# 03_Battery_Management.net
KiCad netlist of a schematic drawn in Altium Designer
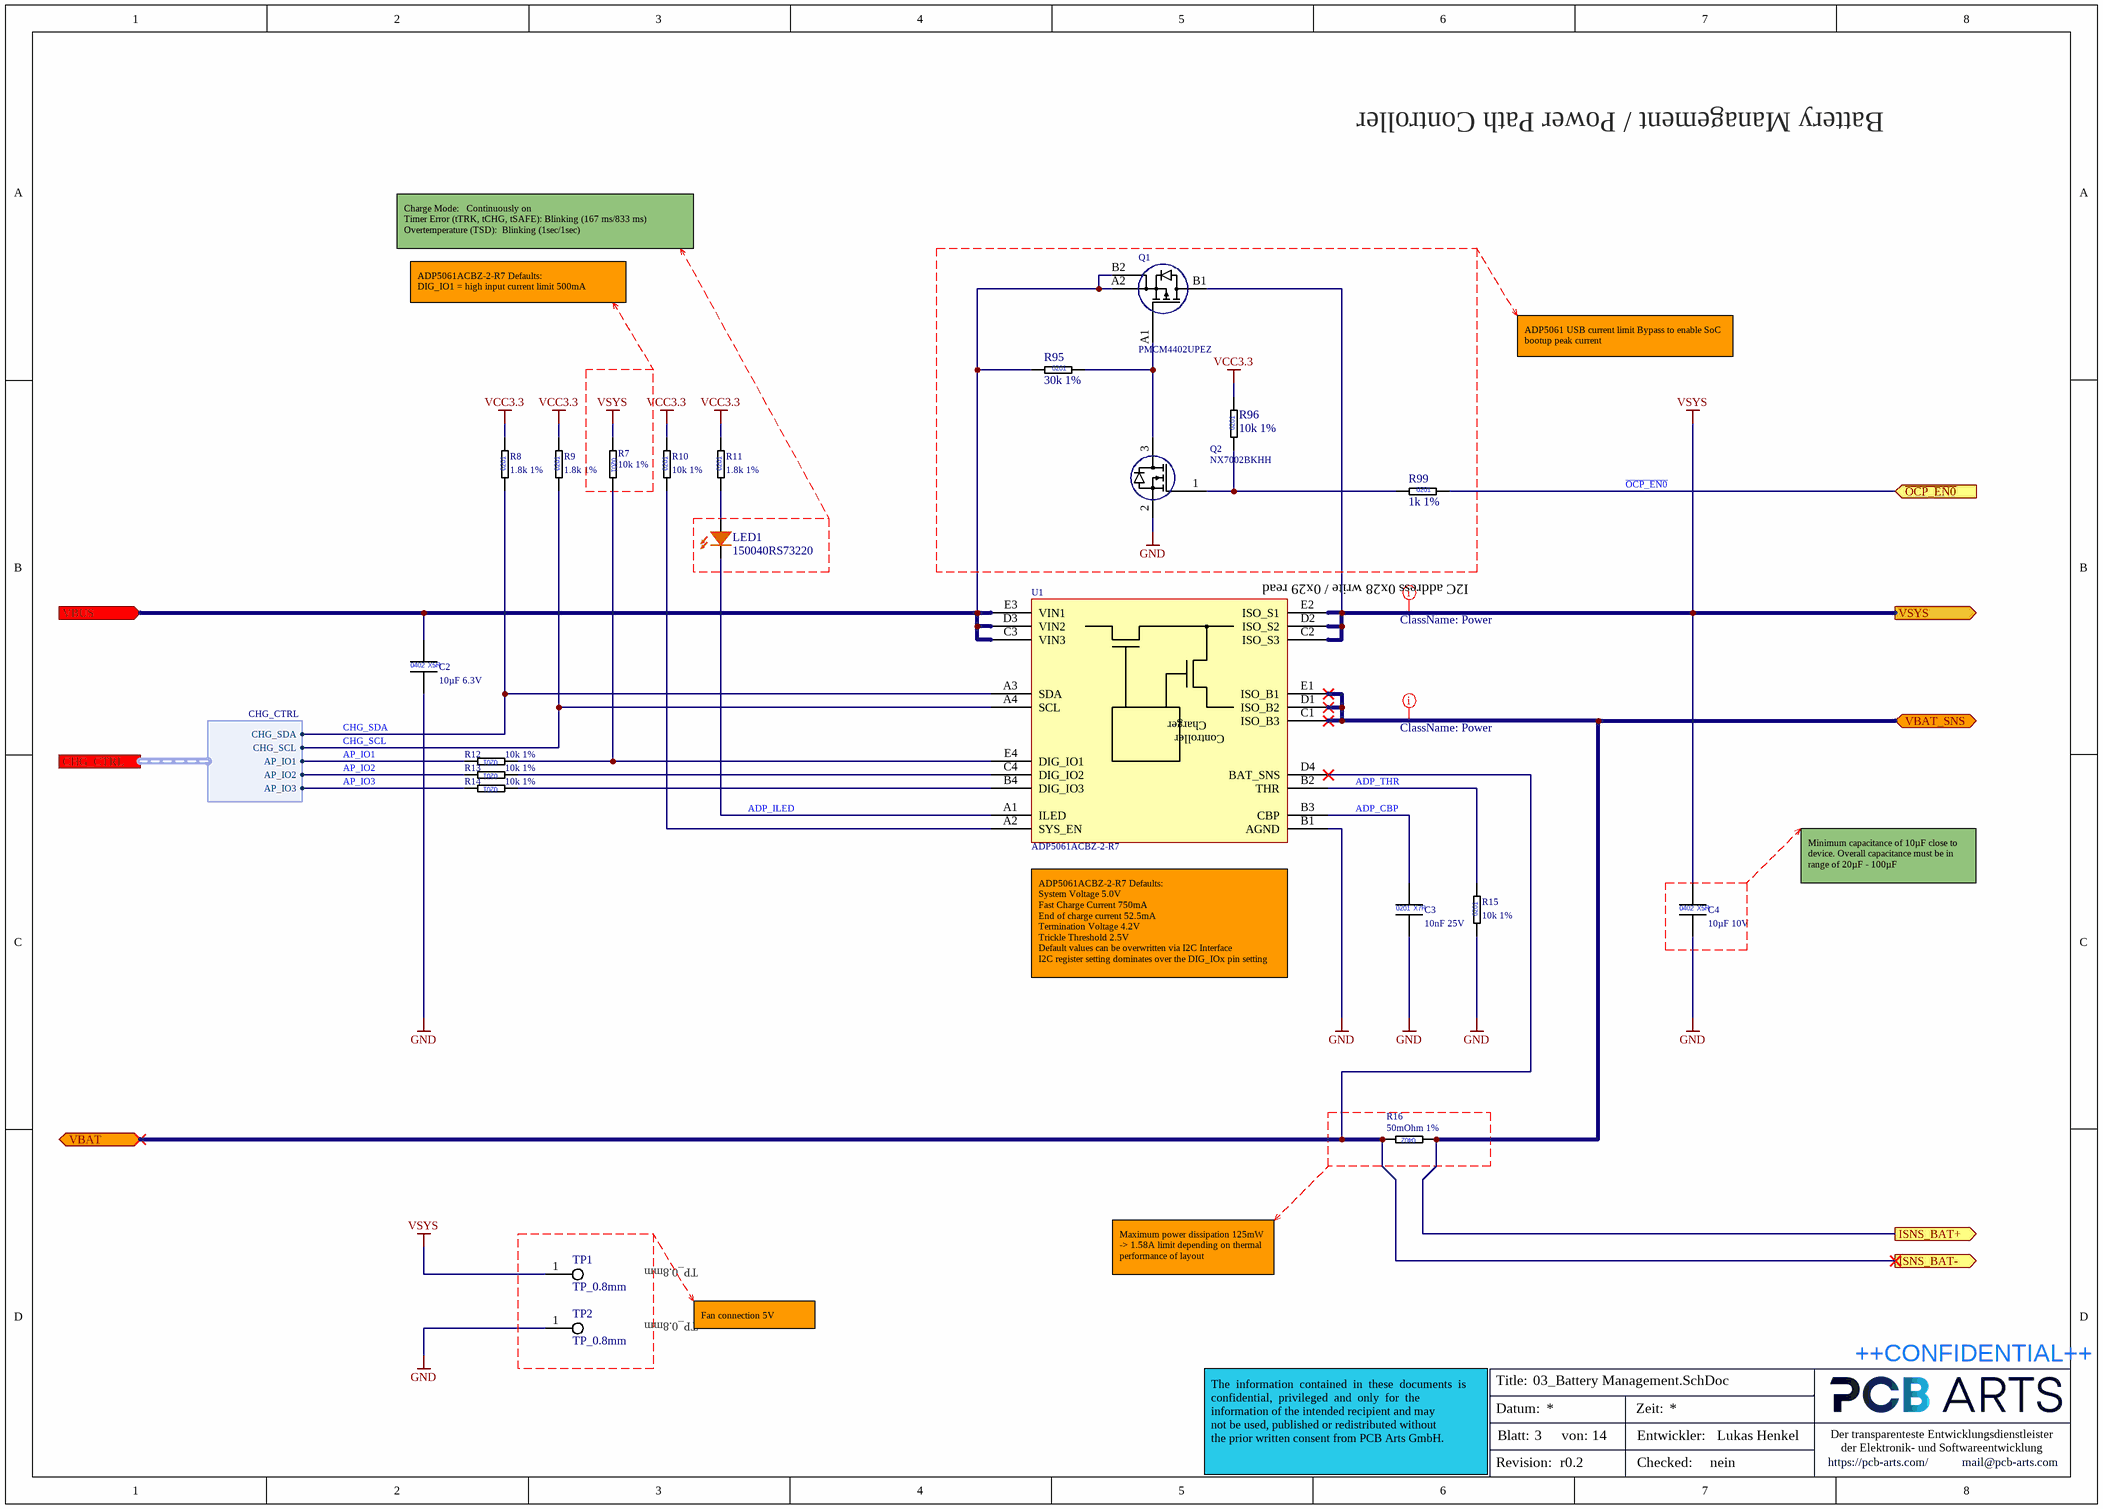
[diagram p0: 03_Battery Management.SchDoc]

(export (version "E")
  (design (tool "Eeschema 10.0.6"))
  (components
    (comp (ref "C2")
      (value "10µF 6.3V")
      (footprint "Zynq-Feather-HD:CAPC1005X06L")
      (description "Multilayer Ceramic Capacitors MLCC - SMD/SMT 0402 6.3VDC")
      (libsource (lib "Zynq-Feather-HD") (part "CAP_0402_10µ_6.3V"))
    )
    (comp (ref "C3")
      (value "10nF 25V")
      (footprint "Zynq-Feather-HD:CAPC0603X03L")
      (description "Multilayer Ceramic Capacitors MLCC - SMD/SMT 0201 25VDC")
      (libsource (lib "Zynq-Feather-HD") (part "CAP_0201_10nF_25V"))
    )
    (comp (ref "C4")
      (value "10µF 10V")
      (footprint "Zynq-Feather-HD:CAPC1005X06L")
      (description "Multilayer Ceramic Capacitors MLCC - SMD/SMT 0402 10VDC")
      (libsource (lib "Zynq-Feather-HD") (part "CAP_0402_10µ_10V"))
    )
    (comp (ref "LED1")
      (value "150040RS73220")
      (footprint "Zynq-Feather-HD:WL-SMCC_0402_H=0.25mm")
      (description "Standard LEDs - SMD WL-SMCC SMT LED Mono-color")
      (libsource (lib "Zynq-Feather-HD") (part "150040RS73220_SMD WL-SMCC SMT LED Mono-color"))
    )
    (comp (ref "Q1")
      (value "PMCM4402UPEZ")
      (footprint "zynq-feather-hd:BGA4C40P2X2_78X78X38")
      (description "20 V, P-channel Trench MOSFET")
      (libsource (lib "Zynq-Feather-HD") (part "PMCM4402UPEZ_PMOS 20V P-channel Trench MOSFET"))
    )
    (comp (ref "Q2")
      (value "NX7002BKHH")
      (footprint "Zynq-Feather-HD:DFN0606-3")
      (description "60 V, N-channel Trench MOSFET 2.8Ohm")
      (libsource (lib "Zynq-Feather-HD") (part "NX7002BKHH_NMOS 60V N-channel Trench MOSFET"))
    )
    (comp (ref "R7")
      (value "10k 1%")
      (footprint "Zynq-Feather-HD:RESC0603X03L")
      (description "Thick Film Resistors - SMD 10K OHM 1%")
      (libsource (lib "Zynq-Feather-HD") (part "RES_0201_10k_1%"))
    )
    (comp (ref "R8")
      (value "1.8k 1%")
      (footprint "Zynq-Feather-HD:RESC0603X03L")
      (description "Thick Film Resistors - SMD 1.8K OHM 1%")
      (libsource (lib "Zynq-Feather-HD") (part "RES_0201_1.8k_1%"))
    )
    (comp (ref "R9")
      (value "1.8k 1%")
      (footprint "Zynq-Feather-HD:RESC0603X03L")
      (description "Thick Film Resistors - SMD 1.8K OHM 1%")
      (libsource (lib "Zynq-Feather-HD") (part "RES_0201_1.8k_1%"))
    )
    (comp (ref "R10")
      (value "10k 1%")
      (footprint "Zynq-Feather-HD:RESC0603X03L")
      (description "Thick Film Resistors - SMD 10K OHM 1%")
      (libsource (lib "Zynq-Feather-HD") (part "RES_0201_10k_1%"))
    )
    (comp (ref "R11")
      (value "1.8k 1%")
      (footprint "Zynq-Feather-HD:RESC0603X03L")
      (description "Thick Film Resistors - SMD 1.8K OHM 1%")
      (libsource (lib "Zynq-Feather-HD") (part "RES_0201_1.8k_1%"))
    )
    (comp (ref "R12")
      (value "10k 1%")
      (footprint "Zynq-Feather-HD:RESC0603X03L")
      (description "Thick Film Resistors - SMD 10K OHM 1%")
      (libsource (lib "Zynq-Feather-HD") (part "RES_0201_10k_1%"))
    )
    (comp (ref "R13")
      (value "10k 1%")
      (footprint "Zynq-Feather-HD:RESC0603X03L")
      (description "Thick Film Resistors - SMD 10K OHM 1%")
      (libsource (lib "Zynq-Feather-HD") (part "RES_0201_10k_1%"))
    )
    (comp (ref "R14")
      (value "10k 1%")
      (footprint "Zynq-Feather-HD:RESC0603X03L")
      (description "Thick Film Resistors - SMD 10K OHM 1%")
      (libsource (lib "Zynq-Feather-HD") (part "RES_0201_10k_1%"))
    )
    (comp (ref "R15")
      (value "10k 1%")
      (footprint "Zynq-Feather-HD:RESC0603X03L")
      (description "Thick Film Resistors - SMD 10K OHM 1%")
      (libsource (lib "Zynq-Feather-HD") (part "RES_0201_10k_1%"))
    )
    (comp (ref "R16")
      (value "50mOhm 1%")
      (footprint "Zynq-Feather-HD:RESC1005X04L")
      (description "Thick Film Resistors - SMD 50mOHM 1%")
      (libsource (lib "Zynq-Feather-HD") (part "RES_0402_50mR_1%"))
    )
    (comp (ref "R95")
      (value "30k 1%")
      (footprint "Zynq-Feather-HD:RESC0603X03L")
      (description "Thick Film Resistors - SMD 30K OHM 1%")
      (libsource (lib "Zynq-Feather-HD") (part "RES_0201_30k_1%"))
    )
    (comp (ref "R96")
      (value "10k 1%")
      (footprint "Zynq-Feather-HD:RESC0603X03L")
      (description "Thick Film Resistors - SMD 10K OHM 1%")
      (libsource (lib "Zynq-Feather-HD") (part "RES_0201_10k_1%"))
    )
    (comp (ref "R99")
      (value "1k 1%")
      (footprint "Zynq-Feather-HD:RESC0603X03L")
      (description "Thick Film Resistors - SMD 1K OHM 1%")
      (libsource (lib "Zynq-Feather-HD") (part "RES_0201_1k_1%"))
    )
    (comp (ref "TP1")
      (value "TP_0.8mm")
      (footprint "Zynq-Feather-HD:TP_0.8mm")
      (description "Testpoint 0.8mm diameter, with 3D Mark")
      (libsource (lib "Zynq-Feather-HD") (part "TP_0.8mm_Tespoint"))
    )
    (comp (ref "TP2")
      (value "TP_0.8mm")
      (footprint "Zynq-Feather-HD:TP_0.8mm")
      (description "Testpoint 0.8mm diameter, with 3D Mark")
      (libsource (lib "Zynq-Feather-HD") (part "TP_0.8mm_Tespoint"))
    )
    (comp (ref "U1")
      (value "ADP5061ACBZ-2-R7")
      (footprint "Zynq-Feather-HD:BGA20C50P4X5_200X260X66")
      (description "Tiny, I2C Programmable, Linear Battery Charger with Power Path and USB Mode Compatibility")
      (libsource (lib "Zynq-Feather-HD") (part "ADP5061ACBZ-2-R7_I2C Programmable, Linear Battery Charger"))
    )
  )
  (nets
    (net (code "2") (name "/ADP_CBP") (class "Default")
      (node (ref "C3") (pin "1") (pinfunction "1_1") (pintype "passive"))
      (node (ref "U1") (pin "B3") (pinfunction "CBP_B3") (pintype "passive"))
    )
    (net (code "3") (name "/ADP_ILED") (class "Default")
      (node (ref "LED1") (pin "1") (pinfunction "1_1") (pintype "passive"))
      (node (ref "U1") (pin "A1") (pinfunction "ILED_A1") (pintype "passive"))
    )
    (net (code "4") (name "/ADP_THR") (class "Default")
      (node (ref "R15") (pin "2") (pinfunction "2_2") (pintype "passive"))
      (node (ref "U1") (pin "B2") (pinfunction "THR_B2") (pintype "passive"))
    )
    (net (code "5") (name "/AP_IO1") (class "Default")
      (node (ref "R12") (pin "2") (pinfunction "2_2") (pintype "passive"))
    )
    (net (code "6") (name "/AP_IO2") (class "Default")
      (node (ref "R13") (pin "2") (pinfunction "2_2") (pintype "passive"))
    )
    (net (code "7") (name "/AP_IO3") (class "Default")
      (node (ref "R14") (pin "2") (pinfunction "2_2") (pintype "passive"))
    )
    (net (code "8") (name "/CHG_SCL") (class "Default")
      (node (ref "R9") (pin "1") (pinfunction "1_1") (pintype "passive"))
      (node (ref "U1") (pin "A4") (pinfunction "SCL_A4") (pintype "passive"))
    )
    (net (code "9") (name "/CHG_SDA") (class "Default")
      (node (ref "R8") (pin "1") (pinfunction "1_1") (pintype "passive"))
      (node (ref "U1") (pin "A3") (pinfunction "SDA_A3") (pintype "passive"))
    )
    (net (code "10") (name "/ISNS_BAT+") (class "Default")
      (node (ref "R16") (pin "1") (pinfunction "1_1") (pintype "passive"))
      (node (ref "U1") (pin "C1") (pinfunction "ISO_B3_C1") (pintype "passive"))
      (node (ref "U1") (pin "D1") (pinfunction "ISO_B2_D1") (pintype "passive"))
      (node (ref "U1") (pin "E1") (pinfunction "ISO_B1_E1") (pintype "passive"))
    )
    (net (code "11") (name "/ISNS_BAT-") (class "Default")
      (node (ref "R16") (pin "2") (pinfunction "2_2") (pintype "passive"))
      (node (ref "U1") (pin "D4") (pinfunction "BAT_SNS_D4") (pintype "passive"))
    )
    (net (code "12") (name "/VBUS") (class "Default")
      (node (ref "C2") (pin "1") (pinfunction "1_1") (pintype "passive"))
      (node (ref "Q1") (pin "A2") (pinfunction "Source_A2") (pintype "passive"))
      (node (ref "Q1") (pin "B2") (pinfunction "Source_B2") (pintype "passive"))
      (node (ref "R95") (pin "1") (pinfunction "1_1") (pintype "passive"))
      (node (ref "U1") (pin "C3") (pinfunction "VIN3_C3") (pintype "passive"))
      (node (ref "U1") (pin "D3") (pinfunction "VIN2_D3") (pintype "passive"))
      (node (ref "U1") (pin "E3") (pinfunction "VIN1_E3") (pintype "passive"))
    )
    (net (code "14") (name "/~{OCP_EN0}") (class "Default")
      (node (ref "R99") (pin "2") (pinfunction "2_2") (pintype "passive"))
    )
    (net (code "15") (name "GND") (class "Default")
      (node (ref "C2") (pin "2") (pinfunction "2_2") (pintype "passive"))
      (node (ref "C3") (pin "2") (pinfunction "2_2") (pintype "passive"))
      (node (ref "C4") (pin "2") (pinfunction "2_2") (pintype "passive"))
      (node (ref "Q2") (pin "2") (pinfunction "Source_2") (pintype "passive"))
      (node (ref "R15") (pin "1") (pinfunction "1_1") (pintype "passive"))
      (node (ref "TP2") (pin "1") (pinfunction "1_1") (pintype "passive"))
      (node (ref "U1") (pin "B1") (pinfunction "AGND_B1") (pintype "passive"))
    )
    (net (code "16") (name "Net-(LED1-Pad2)") (class "Default")
      (node (ref "LED1") (pin "2") (pinfunction "2_2") (pintype "passive"))
      (node (ref "R11") (pin "1") (pinfunction "1_1") (pintype "passive"))
    )
    (net (code "17") (name "Net-(Q1-Gate)") (class "Default")
      (node (ref "Q1") (pin "A1") (pinfunction "Gate_A1") (pintype "passive"))
      (node (ref "Q2") (pin "3") (pinfunction "Drain_3") (pintype "passive"))
      (node (ref "R95") (pin "2") (pinfunction "2_2") (pintype "passive"))
    )
    (net (code "18") (name "Net-(Q2-Gate)") (class "Default")
      (node (ref "Q2") (pin "1") (pinfunction "Gate_1") (pintype "passive"))
      (node (ref "R96") (pin "1") (pinfunction "1_1") (pintype "passive"))
      (node (ref "R99") (pin "1") (pinfunction "1_1") (pintype "passive"))
    )
    (net (code "19") (name "Net-(U1-DIG_IO1)") (class "Default")
      (node (ref "R12") (pin "1") (pinfunction "1_1") (pintype "passive"))
      (node (ref "R7") (pin "2") (pinfunction "2_2") (pintype "passive"))
      (node (ref "U1") (pin "E4") (pinfunction "DIG_IO1_E4") (pintype "passive"))
    )
    (net (code "20") (name "Net-(U1-DIG_IO2)") (class "Default")
      (node (ref "R13") (pin "1") (pinfunction "1_1") (pintype "passive"))
      (node (ref "U1") (pin "C4") (pinfunction "DIG_IO2_C4") (pintype "passive"))
    )
    (net (code "21") (name "Net-(U1-DIG_IO3)") (class "Default")
      (node (ref "R14") (pin "1") (pinfunction "1_1") (pintype "passive"))
      (node (ref "U1") (pin "B4") (pinfunction "DIG_IO3_B4") (pintype "passive"))
    )
    (net (code "22") (name "Net-(U1-SYS_EN)") (class "Default")
      (node (ref "R10") (pin "1") (pinfunction "1_1") (pintype "passive"))
      (node (ref "U1") (pin "A2") (pinfunction "SYS_EN_A2") (pintype "passive"))
    )
    (net (code "23") (name "VCC3.3") (class "Default")
      (node (ref "R10") (pin "2") (pinfunction "2_2") (pintype "passive"))
      (node (ref "R11") (pin "2") (pinfunction "2_2") (pintype "passive"))
      (node (ref "R8") (pin "2") (pinfunction "2_2") (pintype "passive"))
      (node (ref "R9") (pin "2") (pinfunction "2_2") (pintype "passive"))
      (node (ref "R96") (pin "2") (pinfunction "2_2") (pintype "passive"))
    )
    (net (code "24") (name "VSYS") (class "Default")
      (node (ref "C4") (pin "1") (pinfunction "1_1") (pintype "passive"))
      (node (ref "Q1") (pin "B1") (pinfunction "Drain_B1") (pintype "passive"))
      (node (ref "R7") (pin "1") (pinfunction "1_1") (pintype "passive"))
      (node (ref "TP1") (pin "1") (pinfunction "1_1") (pintype "passive"))
      (node (ref "U1") (pin "C2") (pinfunction "ISO_S3_C2") (pintype "passive"))
      (node (ref "U1") (pin "D2") (pinfunction "ISO_S2_D2") (pintype "passive"))
      (node (ref "U1") (pin "E2") (pinfunction "ISO_S1_E2") (pintype "passive"))
    )
  )
)
